# Input_Output.net
KiCad netlist of a schematic drawn in Altium Designer
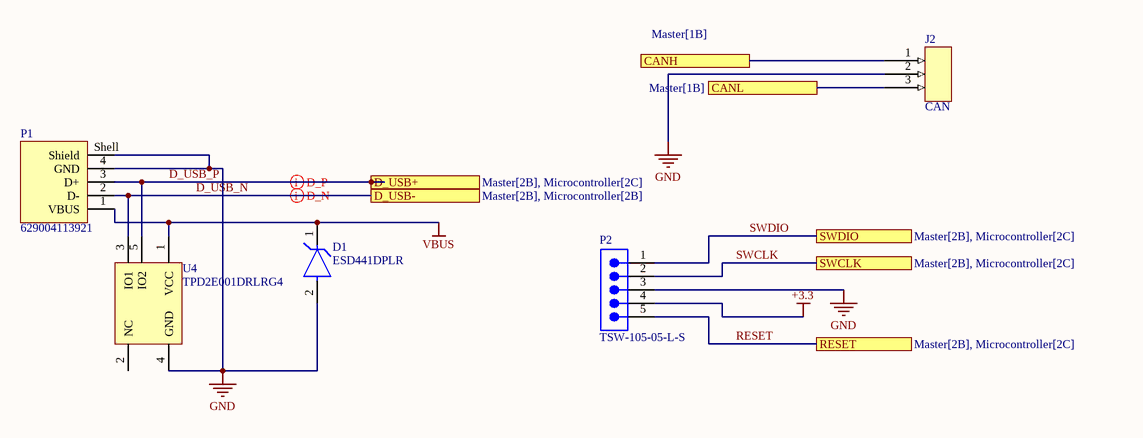
[diagram p0: Input_Output.SchDoc]

(export (version "E")
  (design (tool "Eeschema 10.0.6"))
  (components
    (comp (ref "D1")
      (value "ESD441DPLR")
      (footprint "FP-DPL0002A-MFG")
      (description "ESD441DPLR 1-pF, 5.5-V, 30-KV ESD protection device in 0201 package 2-X2SON -40 to 125")
      (libsource (lib "Altium Content Vault") (part "66ee42db3b8e3650e8893baa18e0b41"))
    )
    (comp (ref "J2")
      (value "CAN")
      (footprint "3 pin 2.54mm header-Footprint-1")
      (description "3 pin header for jumpers connectors 2.54mm pitch.")
      (libsource (lib "Sooner Competitive Robotics") (part "3 pin 2.54mm header-Symbol-1"))
    )
    (comp (ref "P1")
      (value "629004113921")
      (footprint "629004113921")
      (libsource (lib "Altium Content Vault") (part "USB 2.0_Type A_Plug_1 Port"))
    )
    (comp (ref "P2")
      (value "TSW-105-05-L-S")
      (footprint "SMTC-TSW-105-05-X-S")
      (description "0.025\" SQ Post Header, Through-hole, Vertical, -55 to 125 degC, 2.54 mm Pitch, 5-Pin, Male, RoHS")
      (fields (field (name "MANUFACTURER") "Samtec"))
      (libsource (lib "Altium Content Vault") (part "SMTC-TSW-105-05-X-S"))
    )
    (comp (ref "U4")
      (value "TPD2E001DRLRG4")
      (footprint "DRL0005A_L")
      (fields (field (name "MANUFACTURER") "Texas Instruments"))
      (libsource (lib "Altium Content Vault") (part "TI-TPD2E001-SOT_DRL-5"))
    )
  )
  (nets
    (net (code "1") (name "+3.3") (class "Default")
      (node (ref "P2") (pin "4") (pinfunction "4_4") (pintype "passive"))
    )
    (net (code "2") (name "/CANH") (class "Default")
      (node (ref "J2") (pin "1") (pinfunction "1_1") (pintype "input"))
    )
    (net (code "3") (name "/CANL") (class "Default")
      (node (ref "J2") (pin "3") (pinfunction "3_3") (pintype "input"))
    )
    (net (code "4") (name "/D_USB_N") (class "Default")
      (node (ref "P1") (pin "2") (pinfunction "D-_2") (pintype "passive"))
      (node (ref "U4") (pin "3") (pinfunction "IO1_3") (pintype "passive"))
    )
    (net (code "5") (name "/D_USB_P") (class "Default")
      (node (ref "P1") (pin "3") (pinfunction "D+_3") (pintype "passive"))
      (node (ref "U4") (pin "5") (pinfunction "IO2_5") (pintype "passive"))
    )
    (net (code "6") (name "/RESET") (class "Default")
      (node (ref "P2") (pin "5") (pinfunction "5_5") (pintype "passive"))
    )
    (net (code "7") (name "/SWCLK") (class "Default")
      (node (ref "P2") (pin "2") (pinfunction "2_2") (pintype "passive"))
    )
    (net (code "8") (name "/SWDIO") (class "Default")
      (node (ref "P2") (pin "1") (pinfunction "1_1") (pintype "passive"))
    )
    (net (code "9") (name "GND") (class "Default")
      (node (ref "D1") (pin "2") (pinfunction "GND_2") (pintype "passive"))
      (node (ref "J2") (pin "2") (pinfunction "2_2") (pintype "input"))
      (node (ref "P1") (pin "4") (pinfunction "GND_4") (pintype "passive"))
      (node (ref "P1") (pin "Shell") (pinfunction "Shield_Shell") (pintype "passive"))
      (node (ref "P2") (pin "3") (pinfunction "3_3") (pintype "passive"))
      (node (ref "U4") (pin "4") (pinfunction "GND_4") (pintype "power_in"))
    )
    (net (code "10") (name "VBUS") (class "Default")
      (node (ref "D1") (pin "1") (pinfunction "IO_1") (pintype "passive"))
      (node (ref "P1") (pin "1") (pinfunction "VBUS_1") (pintype "passive"))
      (node (ref "U4") (pin "1") (pinfunction "VCC_1") (pintype "power_in"))
    )
    (net (code "11") (name "unconnected-(U4-NC-Pad2)") (class "Default")
      (node (ref "U4") (pin "2") (pinfunction "NC_2") (pintype "passive"))
    )
  )
)
